# POWER_FLASH_POWER_MANAGE.net
KiCad netlist of a schematic drawn in Altium Designer
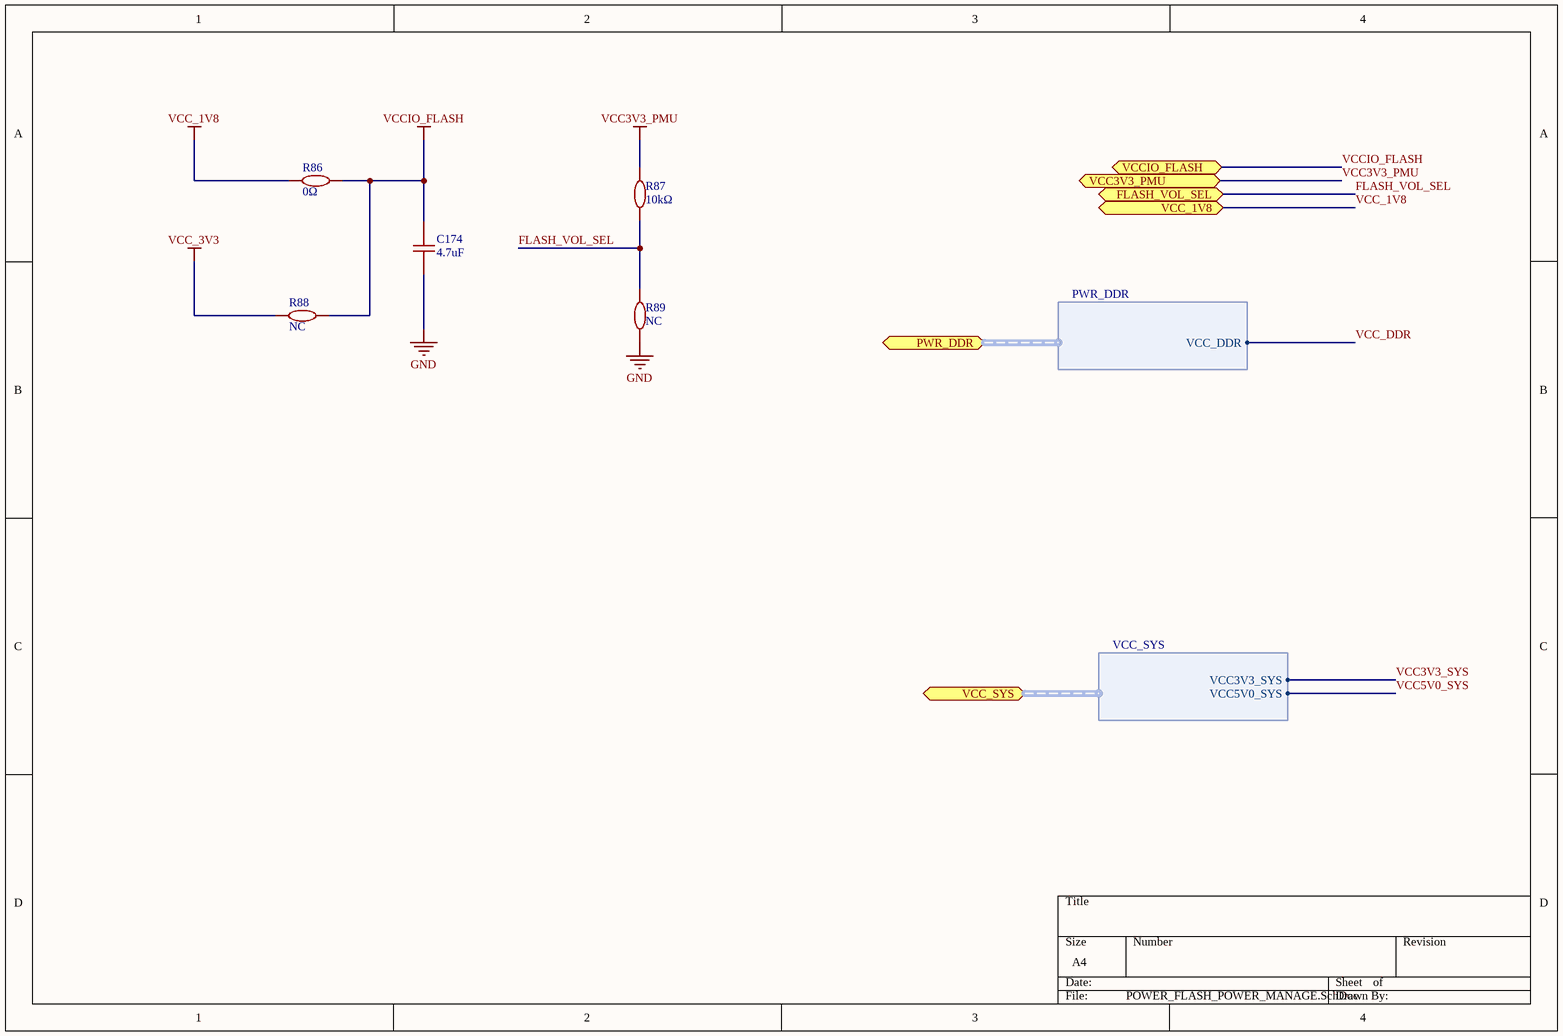
[diagram p0: POWER_FLASH_POWER_MANAGE.SchDoc]

(export (version "E")
  (design (tool "Eeschema 10.0.6"))
  (components
    (comp (ref "C174")
      (value "4.7uF")
      (footprint "C0402")
      (description "10V 4.7uF X5R ±20% 0402 Ceramic Capacitors ROHS")
      (libsource (lib "RLC") (part "4.7uF"))
    )
    (comp (ref "R86")
      (value "0Ω")
      (footprint "R0402")
      (description "0Ω 62.5mW 50V Thick Film Resistor ±1% 0402 Chip Resistor - Surface Mount ROHS")
      (libsource (lib "RLC") (part "0Ω"))
    )
    (comp (ref "R87")
      (value "10kΩ")
      (footprint "R0402")
      (description "62.5mW 10kΩ 50V ±100ppm/℃ Thick Film Resistor ±1% 0402 Chip Resistor - Surface Mount ROHS")
      (libsource (lib "RLC") (part "10kΩ"))
    )
    (comp (ref "R88")
      (value "NC")
      (footprint "R0402")
      (description "0Ω 62.5mW 50V Thick Film Resistor ±1% 0402 Chip Resistor - Surface Mount ROHS")
      (libsource (lib "RLC") (part "0Ω"))
    )
    (comp (ref "R89")
      (value "NC")
      (footprint "R0402")
      (description "0Ω 62.5mW 50V Thick Film Resistor ±1% 0402 Chip Resistor - Surface Mount ROHS")
      (libsource (lib "RLC") (part "0Ω"))
    )
  )
  (nets
    (net (code "3") (name "/FLASH_VOL_SEL") (class "Default")
      (node (ref "R87") (pin "1") (pinfunction "1_1") (pintype "passive"))
      (node (ref "R89") (pin "2") (pinfunction "2_2") (pintype "passive"))
    )
    (net (code "9") (name "GND") (class "Default")
      (node (ref "C174") (pin "1") (pinfunction "1_1") (pintype "passive"))
      (node (ref "R89") (pin "1") (pinfunction "1_1") (pintype "passive"))
    )
    (net (code "10") (name "VCC3V3_PMU") (class "Default")
      (node (ref "R87") (pin "2") (pinfunction "2_2") (pintype "passive"))
    )
    (net (code "11") (name "VCCIO_FLASH") (class "Default")
      (node (ref "C174") (pin "2") (pinfunction "2_2") (pintype "passive"))
      (node (ref "R86") (pin "2") (pinfunction "2_2") (pintype "passive"))
      (node (ref "R88") (pin "2") (pinfunction "2_2") (pintype "passive"))
    )
    (net (code "12") (name "VCC_1V8") (class "Default")
      (node (ref "R86") (pin "1") (pinfunction "1_1") (pintype "passive"))
    )
    (net (code "13") (name "VCC_3V3") (class "Default")
      (node (ref "R88") (pin "1") (pinfunction "1_1") (pintype "passive"))
    )
  )
)
